# 2019_Dashboard_rev_1-15-19.net
KiCad netlist of a schematic drawn in EAGLE
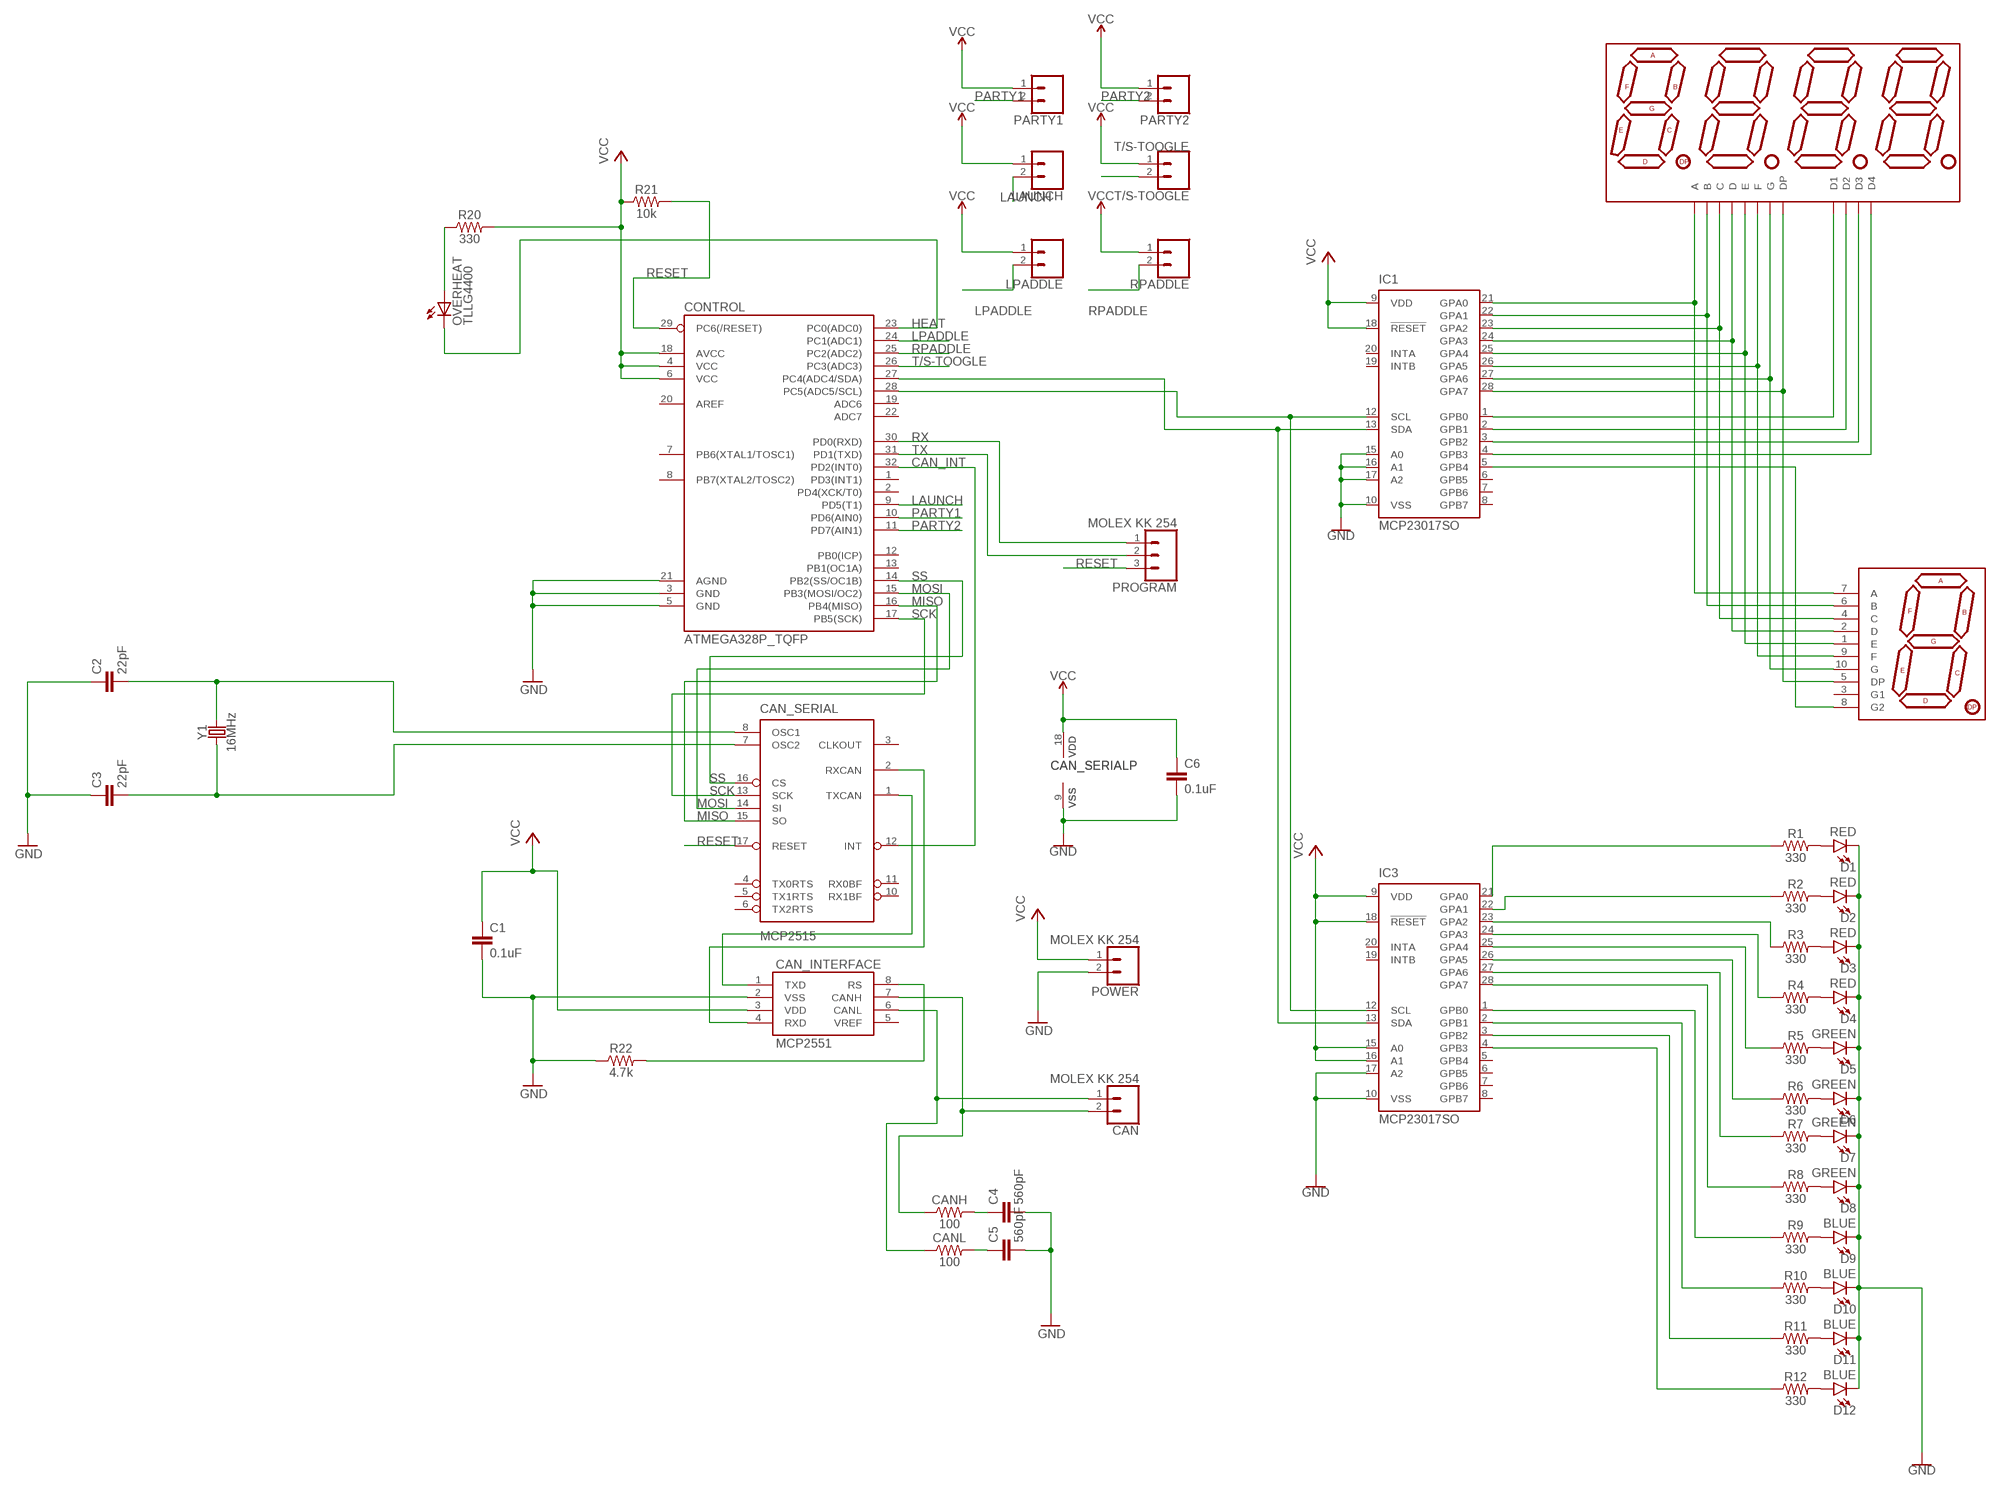
[diagram p0: schematic, sheet 1]

(export (version "E")
  (design (tool "Eeschema 10.0.6"))
  (components
    (comp (ref "C1")
      (value "0.1uF")
      (footprint "eagle-import:0603")
      (libsource (lib "eagle-import") (part "0.1UF-0603-25V-(+80/-20%)"))
    )
    (comp (ref "C2")
      (value "22pF")
      (footprint "eagle-import:0603")
      (libsource (lib "eagle-import") (part "22PF-0603-50V-5%"))
    )
    (comp (ref "C3")
      (value "22pF")
      (footprint "eagle-import:0603")
      (libsource (lib "eagle-import") (part "22PF-0603-50V-5%"))
    )
    (comp (ref "C4")
      (value "560pF")
      (footprint "eagle-import:0603")
      (libsource (lib "eagle-import") (part "560PF-0603-50V-5%"))
    )
    (comp (ref "C5")
      (value "560pF")
      (footprint "eagle-import:0603")
      (libsource (lib "eagle-import") (part "560PF-0603-50V-5%"))
    )
    (comp (ref "C6")
      (value "0.1uF")
      (footprint "eagle-import:0402")
      (libsource (lib "eagle-import") (part "0.1UF-0402-16V-10%"))
    )
    (comp (ref "CAN")
      (value "MOLEX KK 254")
      (footprint "eagle-import:1X02")
      (libsource (lib "eagle-import") (part "CONN_02"))
    )
    (comp (ref "CANH")
      (value "100")
      (footprint "eagle-import:0603")
      (libsource (lib "eagle-import") (part "100OHM-0603-1/4W-5%"))
    )
    (comp (ref "CANL")
      (value "100")
      (footprint "eagle-import:0603")
      (libsource (lib "eagle-import") (part "100OHM-0603-1/4W-5%"))
    )
    (comp (ref "CAN_INTERFACE")
      (value "MCP2551")
      (footprint "eagle-import:SO08")
      (libsource (lib "eagle-import") (part "MCP2551"))
    )
    (comp (ref "CAN_SERIAL")
      (value "MCP2515")
      (footprint "eagle-import:SO18W")
      (libsource (lib "eagle-import") (part "MCP2515(MCP2510)SO"))
    )
    (comp (ref "CONTROL")
      (value "ATMEGA328P_TQFP")
      (footprint "eagle-import:TQFP32-08")
      (libsource (lib "eagle-import") (part "ATMEGA328P_TQFP"))
    )
    (comp (ref "D1")
      (value "RED")
      (footprint "eagle-import:LED-1206")
      (libsource (lib "eagle-import") (part "LED-RED1206"))
    )
    (comp (ref "D2")
      (value "RED")
      (footprint "eagle-import:LED-1206")
      (libsource (lib "eagle-import") (part "LED-RED1206"))
    )
    (comp (ref "D3")
      (value "RED")
      (footprint "eagle-import:LED-1206")
      (libsource (lib "eagle-import") (part "LED-RED1206"))
    )
    (comp (ref "D4")
      (value "RED")
      (footprint "eagle-import:LED-1206")
      (libsource (lib "eagle-import") (part "LED-RED1206"))
    )
    (comp (ref "D5")
      (value "GREEN")
      (footprint "eagle-import:LED-1206")
      (libsource (lib "eagle-import") (part "LED-GREENLILYPAD"))
    )
    (comp (ref "D6")
      (value "GREEN")
      (footprint "eagle-import:LED-1206")
      (libsource (lib "eagle-import") (part "LED-GREENLILYPAD"))
    )
    (comp (ref "D7")
      (value "GREEN")
      (footprint "eagle-import:LED-1206")
      (libsource (lib "eagle-import") (part "LED-GREENLILYPAD"))
    )
    (comp (ref "D8")
      (value "GREEN")
      (footprint "eagle-import:LED-1206")
      (libsource (lib "eagle-import") (part "LED-GREENLILYPAD"))
    )
    (comp (ref "D9")
      (value "BLUE")
      (footprint "eagle-import:LED-1206")
      (libsource (lib "eagle-import") (part "LED-BLUE1206"))
    )
    (comp (ref "D10")
      (value "BLUE")
      (footprint "eagle-import:LED-1206")
      (libsource (lib "eagle-import") (part "LED-BLUE1206"))
    )
    (comp (ref "D11")
      (value "BLUE")
      (footprint "eagle-import:LED-1206")
      (libsource (lib "eagle-import") (part "LED-BLUE1206"))
    )
    (comp (ref "D12")
      (value "BLUE")
      (footprint "eagle-import:LED-1206")
      (libsource (lib "eagle-import") (part "LED-BLUE1206"))
    )
    (comp (ref "DISP1")
      (value "ATA8041ARBJ")
      (footprint "eagle-import:7-SEGMENT-4DIGIT-20MM")
      (libsource (lib "eagle-import") (part "7-SEGMENT-4DIGIT-20MM-RED"))
    )
    (comp (ref "IC1")
      (value "MCP23017SO")
      (footprint "eagle-import:SO28W")
      (libsource (lib "eagle-import") (part "MCP23017SO"))
    )
    (comp (ref "IC3")
      (value "MCP23017SO")
      (footprint "eagle-import:SO28W")
      (libsource (lib "eagle-import") (part "MCP23017SO"))
    )
    (comp (ref "LAUNCH")
      (value "CONN_02LOCK")
      (footprint "eagle-import:1X02_LOCK")
      (libsource (lib "eagle-import") (part "CONN_02LOCK"))
    )
    (comp (ref "LPADDLE")
      (value "CONN_02LOCK")
      (footprint "eagle-import:1X02_LOCK")
      (libsource (lib "eagle-import") (part "CONN_02LOCK"))
    )
    (comp (ref "OVERHEAT")
      (value "TLLG4400")
      (footprint "eagle-import:LED3MM")
      (fields (field (name "MF") "VISHAY SEMICONDUCTOR"))
      (libsource (lib "eagle-import") (part "TLLG4400"))
    )
    (comp (ref "PARTY1")
      (value "CONN_02LOCK")
      (footprint "eagle-import:1X02_LOCK")
      (libsource (lib "eagle-import") (part "CONN_02LOCK"))
    )
    (comp (ref "PARTY2")
      (value "CONN_02LOCK")
      (footprint "eagle-import:1X02_LOCK")
      (libsource (lib "eagle-import") (part "CONN_02LOCK"))
    )
    (comp (ref "POWER")
      (value "MOLEX KK 254")
      (footprint "eagle-import:1X02")
      (libsource (lib "eagle-import") (part "CONN_02"))
    )
    (comp (ref "PROGRAM")
      (value "MOLEX KK 254")
      (footprint "eagle-import:1X03")
      (libsource (lib "eagle-import") (part "CONN_03"))
    )
    (comp (ref "R1")
      (value "330")
      (footprint "eagle-import:0603")
      (libsource (lib "eagle-import") (part "330OHM-0603-1/10W-1%"))
    )
    (comp (ref "R2")
      (value "330")
      (footprint "eagle-import:0603")
      (libsource (lib "eagle-import") (part "330OHM-0603-1/10W-1%"))
    )
    (comp (ref "R3")
      (value "330")
      (footprint "eagle-import:0603")
      (libsource (lib "eagle-import") (part "330OHM-0603-1/10W-1%"))
    )
    (comp (ref "R4")
      (value "330")
      (footprint "eagle-import:0603")
      (libsource (lib "eagle-import") (part "330OHM-0603-1/10W-1%"))
    )
    (comp (ref "R5")
      (value "330")
      (footprint "eagle-import:0603")
      (libsource (lib "eagle-import") (part "330OHM-0603-1/10W-1%"))
    )
    (comp (ref "R6")
      (value "330")
      (footprint "eagle-import:0603")
      (libsource (lib "eagle-import") (part "330OHM-0603-1/10W-1%"))
    )
    (comp (ref "R7")
      (value "330")
      (footprint "eagle-import:0603")
      (libsource (lib "eagle-import") (part "330OHM-0603-1/10W-1%"))
    )
    (comp (ref "R8")
      (value "330")
      (footprint "eagle-import:0603")
      (libsource (lib "eagle-import") (part "330OHM-0603-1/10W-1%"))
    )
    (comp (ref "R9")
      (value "330")
      (footprint "eagle-import:0603")
      (libsource (lib "eagle-import") (part "330OHM-0603-1/10W-1%"))
    )
    (comp (ref "R10")
      (value "330")
      (footprint "eagle-import:0603")
      (libsource (lib "eagle-import") (part "330OHM-0603-1/10W-1%"))
    )
    (comp (ref "R11")
      (value "330")
      (footprint "eagle-import:0603")
      (libsource (lib "eagle-import") (part "330OHM-0603-1/10W-1%"))
    )
    (comp (ref "R12")
      (value "330")
      (footprint "eagle-import:0603")
      (libsource (lib "eagle-import") (part "330OHM-0603-1/10W-1%"))
    )
    (comp (ref "R20")
      (value "330")
      (footprint "eagle-import:0603")
      (libsource (lib "eagle-import") (part "330OHM-0603-1/10W-1%"))
    )
    (comp (ref "R21")
      (value "10k")
      (footprint "eagle-import:0603")
      (libsource (lib "eagle-import") (part "10KOHM-0603-1/10W-1%"))
    )
    (comp (ref "R22")
      (value "4.7k")
      (footprint "eagle-import:0603")
      (libsource (lib "eagle-import") (part "4.7KOHM-0603-1/10W-1%"))
    )
    (comp (ref "RPADDLE")
      (value "CONN_02LOCK")
      (footprint "eagle-import:1X02_LOCK")
      (libsource (lib "eagle-import") (part "CONN_02LOCK"))
    )
    (comp (ref "T/S-TOOGLE")
      (value "CONN_02LOCK")
      (footprint "eagle-import:1X02_LOCK")
      (libsource (lib "eagle-import") (part "CONN_02LOCK"))
    )
    (comp (ref "U$1")
      (value "YSD-1601AR4B-8")
      (footprint "eagle-import:7-SEGMENT-1_PTH")
      (libsource (lib "eagle-import") (part "7-SEGMENT-1DIGIT-1INCH-RED"))
    )
    (comp (ref "Y1")
      (value "16MHz")
      (footprint "eagle-import:HC49US")
      (libsource (lib "eagle-import") (part "CRYSTAL-16MHZPTH-HC49US"))
    )
  )
  (nets
    (net (code "1") (name "/CAN_INT") (class "Default")
      (node (ref "CAN_SERIAL") (pin "12") (pinfunction "INT_12") (pintype "output"))
      (node (ref "CONTROL") (pin "32") (pinfunction "PD2(INT0)_32") (pintype "bidirectional"))
    )
    (net (code "2") (name "/HEAT") (class "Default")
      (node (ref "CONTROL") (pin "23") (pinfunction "PC0(ADC0)_23") (pintype "bidirectional"))
      (node (ref "OVERHEAT") (pin "K") (pinfunction "C_K") (pintype "passive"))
    )
    (net (code "3") (name "/LAUNCH") (class "Default")
      (node (ref "CONTROL") (pin "9") (pinfunction "PD5(T1)_9") (pintype "bidirectional"))
      (node (ref "LAUNCH") (pin "2") (pinfunction "2_2") (pintype "passive"))
    )
    (net (code "4") (name "/LPADDLE") (class "Default")
      (node (ref "CONTROL") (pin "24") (pinfunction "PC1(ADC1)_24") (pintype "bidirectional"))
      (node (ref "LPADDLE") (pin "2") (pinfunction "2_2") (pintype "passive"))
    )
    (net (code "5") (name "/MISO") (class "Default")
      (node (ref "CAN_SERIAL") (pin "15") (pinfunction "SO_15") (pintype "output"))
      (node (ref "CONTROL") (pin "16") (pinfunction "PB4(MISO)_16") (pintype "bidirectional"))
    )
    (net (code "6") (name "/MOSI") (class "Default")
      (node (ref "CAN_SERIAL") (pin "14") (pinfunction "SI_14") (pintype "input"))
      (node (ref "CONTROL") (pin "15") (pinfunction "PB3(MOSI/OC2)_15") (pintype "bidirectional"))
    )
    (net (code "7") (name "/PARTY1") (class "Default")
      (node (ref "CONTROL") (pin "10") (pinfunction "PD6(AIN0)_10") (pintype "bidirectional"))
      (node (ref "PARTY1") (pin "2") (pinfunction "2_2") (pintype "passive"))
    )
    (net (code "8") (name "/PARTY2") (class "Default")
      (node (ref "CONTROL") (pin "11") (pinfunction "PD7(AIN1)_11") (pintype "bidirectional"))
      (node (ref "PARTY2") (pin "2") (pinfunction "2_2") (pintype "passive"))
    )
    (net (code "9") (name "/RESET") (class "Default")
      (node (ref "CAN_SERIAL") (pin "17") (pinfunction "RESET_17") (pintype "input"))
      (node (ref "CONTROL") (pin "29") (pinfunction "PC6(/RESET)_29") (pintype "bidirectional"))
      (node (ref "PROGRAM") (pin "3") (pinfunction "3_3") (pintype "passive"))
      (node (ref "R21") (pin "2") (pinfunction "2_2") (pintype "passive"))
    )
    (net (code "10") (name "/RPADDLE") (class "Default")
      (node (ref "CONTROL") (pin "25") (pinfunction "PC2(ADC2)_25") (pintype "bidirectional"))
      (node (ref "RPADDLE") (pin "2") (pinfunction "2_2") (pintype "passive"))
    )
    (net (code "11") (name "/RX") (class "Default")
      (node (ref "CONTROL") (pin "30") (pinfunction "PD0(RXD)_30") (pintype "bidirectional"))
      (node (ref "PROGRAM") (pin "1") (pinfunction "1_1") (pintype "passive"))
    )
    (net (code "12") (name "/SCK") (class "Default")
      (node (ref "CAN_SERIAL") (pin "13") (pinfunction "SCK_13") (pintype "input"))
      (node (ref "CONTROL") (pin "17") (pinfunction "PB5(SCK)_17") (pintype "bidirectional"))
    )
    (net (code "13") (name "/SS") (class "Default")
      (node (ref "CAN_SERIAL") (pin "16") (pinfunction "CS_16") (pintype "input"))
      (node (ref "CONTROL") (pin "14") (pinfunction "PB2(SS/OC1B)_14") (pintype "bidirectional"))
    )
    (net (code "14") (name "/TX") (class "Default")
      (node (ref "CONTROL") (pin "31") (pinfunction "PD1(TXD)_31") (pintype "bidirectional"))
      (node (ref "PROGRAM") (pin "2") (pinfunction "2_2") (pintype "passive"))
    )
    (net (code "15") (name "/T{slash}S-TOOGLE") (class "Default")
      (node (ref "CONTROL") (pin "26") (pinfunction "PC3(ADC3)_26") (pintype "bidirectional"))
      (node (ref "T/S-TOOGLE") (pin "2") (pinfunction "2_2") (pintype "passive"))
    )
    (net (code "16") (name "GND") (class "Default")
      (node (ref "C1") (pin "2") (pinfunction "2_2") (pintype "passive"))
      (node (ref "C2") (pin "1") (pinfunction "1_1") (pintype "passive"))
      (node (ref "C3") (pin "1") (pinfunction "1_1") (pintype "passive"))
      (node (ref "C4") (pin "2") (pinfunction "2_2") (pintype "passive"))
      (node (ref "C5") (pin "2") (pinfunction "2_2") (pintype "passive"))
      (node (ref "C6") (pin "2") (pinfunction "2_2") (pintype "passive"))
      (node (ref "CAN_INTERFACE") (pin "2") (pinfunction "VSS_2") (pintype "bidirectional"))
      (node (ref "CAN_SERIAL") (pin "9") (pinfunction "VSS_9") (pintype "power_in"))
      (node (ref "CONTROL") (pin "21") (pinfunction "AGND_21") (pintype "bidirectional"))
      (node (ref "CONTROL") (pin "3") (pinfunction "GND_3") (pintype "bidirectional"))
      (node (ref "CONTROL") (pin "5") (pinfunction "GND_5") (pintype "bidirectional"))
      (node (ref "D1") (pin "C") (pinfunction "C_C") (pintype "passive"))
      (node (ref "D10") (pin "C") (pinfunction "C_C") (pintype "passive"))
      (node (ref "D11") (pin "C") (pinfunction "C_C") (pintype "passive"))
      (node (ref "D12") (pin "C") (pinfunction "C_C") (pintype "passive"))
      (node (ref "D2") (pin "C") (pinfunction "C_C") (pintype "passive"))
      (node (ref "D3") (pin "C") (pinfunction "C_C") (pintype "passive"))
      (node (ref "D4") (pin "C") (pinfunction "C_C") (pintype "passive"))
      (node (ref "D5") (pin "C") (pinfunction "C_C") (pintype "passive"))
      (node (ref "D6") (pin "C") (pinfunction "C_C") (pintype "passive"))
      (node (ref "D7") (pin "C") (pinfunction "C_C") (pintype "passive"))
      (node (ref "D8") (pin "C") (pinfunction "C_C") (pintype "passive"))
      (node (ref "D9") (pin "C") (pinfunction "C_C") (pintype "passive"))
      (node (ref "IC1") (pin "10") (pinfunction "VSS_10") (pintype "power_in"))
      (node (ref "IC1") (pin "15") (pinfunction "A0_15") (pintype "input"))
      (node (ref "IC1") (pin "16") (pinfunction "A1_16") (pintype "input"))
      (node (ref "IC1") (pin "17") (pinfunction "A2_17") (pintype "input"))
      (node (ref "IC3") (pin "10") (pinfunction "VSS_10") (pintype "power_in"))
      (node (ref "IC3") (pin "17") (pinfunction "A2_17") (pintype "input"))
      (node (ref "POWER") (pin "2") (pinfunction "2_2") (pintype "passive"))
      (node (ref "R22") (pin "1") (pinfunction "1_1") (pintype "passive"))
    )
    (net (code "17") (name "Net-(C4-Pad1)") (class "Default")
      (node (ref "C4") (pin "1") (pinfunction "1_1") (pintype "passive"))
      (node (ref "CANH") (pin "2") (pinfunction "2_2") (pintype "passive"))
    )
    (net (code "18") (name "Net-(C5-Pad1)") (class "Default")
      (node (ref "C5") (pin "1") (pinfunction "1_1") (pintype "passive"))
      (node (ref "CANL") (pin "2") (pinfunction "2_2") (pintype "passive"))
    )
    (net (code "19") (name "Net-(CAN_INTERFACE-CANH)") (class "Default")
      (node (ref "CAN") (pin "2") (pinfunction "2_2") (pintype "passive"))
      (node (ref "CANH") (pin "1") (pinfunction "1_1") (pintype "passive"))
      (node (ref "CAN_INTERFACE") (pin "7") (pinfunction "CANH_7") (pintype "bidirectional"))
    )
    (net (code "20") (name "Net-(CAN_INTERFACE-CANL)") (class "Default")
      (node (ref "CAN") (pin "1") (pinfunction "1_1") (pintype "passive"))
      (node (ref "CANL") (pin "1") (pinfunction "1_1") (pintype "passive"))
      (node (ref "CAN_INTERFACE") (pin "6") (pinfunction "CANL_6") (pintype "bidirectional"))
    )
    (net (code "21") (name "Net-(CAN_INTERFACE-RS)") (class "Default")
      (node (ref "CAN_INTERFACE") (pin "8") (pinfunction "RS_8") (pintype "bidirectional"))
      (node (ref "R22") (pin "2") (pinfunction "2_2") (pintype "passive"))
    )
    (net (code "22") (name "Net-(CAN_INTERFACE-RXD)") (class "Default")
      (node (ref "CAN_INTERFACE") (pin "4") (pinfunction "RXD_4") (pintype "bidirectional"))
      (node (ref "CAN_SERIAL") (pin "2") (pinfunction "RXCAN_2") (pintype "input"))
    )
    (net (code "23") (name "Net-(CAN_INTERFACE-TXD)") (class "Default")
      (node (ref "CAN_INTERFACE") (pin "1") (pinfunction "TXD_1") (pintype "bidirectional"))
      (node (ref "CAN_SERIAL") (pin "1") (pinfunction "TXCAN_1") (pintype "output"))
    )
    (net (code "24") (name "Net-(CAN_SERIALA-OSC1)") (class "Default")
      (node (ref "C2") (pin "2") (pinfunction "2_2") (pintype "passive"))
      (node (ref "CAN_SERIAL") (pin "8") (pinfunction "OSC1_8") (pintype "input"))
      (node (ref "Y1") (pin "2") (pinfunction "2_2") (pintype "passive"))
    )
    (net (code "25") (name "Net-(CAN_SERIALA-OSC2)") (class "Default")
      (node (ref "C3") (pin "2") (pinfunction "2_2") (pintype "passive"))
      (node (ref "CAN_SERIAL") (pin "7") (pinfunction "OSC2_7") (pintype "output"))
      (node (ref "Y1") (pin "1") (pinfunction "1_1") (pintype "passive"))
    )
    (net (code "26") (name "Net-(CONTROL-PC4(ADC4{slash}SDA))") (class "Default")
      (node (ref "CONTROL") (pin "27") (pinfunction "PC4(ADC4/SDA)_27") (pintype "bidirectional"))
      (node (ref "IC1") (pin "13") (pinfunction "SDA_13") (pintype "bidirectional"))
      (node (ref "IC3") (pin "13") (pinfunction "SDA_13") (pintype "bidirectional"))
    )
    (net (code "27") (name "Net-(CONTROL-PC5(ADC5{slash}SCL))") (class "Default")
      (node (ref "CONTROL") (pin "28") (pinfunction "PC5(ADC5/SCL)_28") (pintype "bidirectional"))
      (node (ref "IC1") (pin "12") (pinfunction "SCL_12") (pintype "input"))
      (node (ref "IC3") (pin "12") (pinfunction "SCL_12") (pintype "input"))
    )
    (net (code "28") (name "Net-(D1-PadA)") (class "Default")
      (node (ref "D1") (pin "A") (pinfunction "A_A") (pintype "passive"))
      (node (ref "R1") (pin "2") (pinfunction "2_2") (pintype "passive"))
    )
    (net (code "29") (name "Net-(D2-PadA)") (class "Default")
      (node (ref "D2") (pin "A") (pinfunction "A_A") (pintype "passive"))
      (node (ref "R2") (pin "2") (pinfunction "2_2") (pintype "passive"))
    )
    (net (code "30") (name "Net-(D3-PadA)") (class "Default")
      (node (ref "D3") (pin "A") (pinfunction "A_A") (pintype "passive"))
      (node (ref "R3") (pin "2") (pinfunction "2_2") (pintype "passive"))
    )
    (net (code "31") (name "Net-(D4-PadA)") (class "Default")
      (node (ref "D4") (pin "A") (pinfunction "A_A") (pintype "passive"))
      (node (ref "R4") (pin "2") (pinfunction "2_2") (pintype "passive"))
    )
    (net (code "32") (name "Net-(D5-PadA)") (class "Default")
      (node (ref "D5") (pin "A") (pinfunction "A_A") (pintype "passive"))
      (node (ref "R5") (pin "2") (pinfunction "2_2") (pintype "passive"))
    )
    (net (code "33") (name "Net-(D6-PadA)") (class "Default")
      (node (ref "D6") (pin "A") (pinfunction "A_A") (pintype "passive"))
      (node (ref "R6") (pin "2") (pinfunction "2_2") (pintype "passive"))
    )
    (net (code "34") (name "Net-(D7-PadA)") (class "Default")
      (node (ref "D7") (pin "A") (pinfunction "A_A") (pintype "passive"))
      (node (ref "R7") (pin "2") (pinfunction "2_2") (pintype "passive"))
    )
    (net (code "35") (name "Net-(D8-PadA)") (class "Default")
      (node (ref "D8") (pin "A") (pinfunction "A_A") (pintype "passive"))
      (node (ref "R8") (pin "2") (pinfunction "2_2") (pintype "passive"))
    )
    (net (code "36") (name "Net-(D9-PadA)") (class "Default")
      (node (ref "D9") (pin "A") (pinfunction "A_A") (pintype "passive"))
      (node (ref "R9") (pin "2") (pinfunction "2_2") (pintype "passive"))
    )
    (net (code "37") (name "Net-(D10-PadA)") (class "Default")
      (node (ref "D10") (pin "A") (pinfunction "A_A") (pintype "passive"))
      (node (ref "R10") (pin "2") (pinfunction "2_2") (pintype "passive"))
    )
    (net (code "38") (name "Net-(D11-PadA)") (class "Default")
      (node (ref "D11") (pin "A") (pinfunction "A_A") (pintype "passive"))
      (node (ref "R11") (pin "2") (pinfunction "2_2") (pintype "passive"))
    )
    (net (code "39") (name "Net-(D12-PadA)") (class "Default")
      (node (ref "D12") (pin "A") (pinfunction "A_A") (pintype "passive"))
      (node (ref "R12") (pin "2") (pinfunction "2_2") (pintype "passive"))
    )
    (net (code "40") (name "Net-(DISP1-A)") (class "Default")
      (node (ref "DISP1") (pin "11") (pinfunction "A_11") (pintype "bidirectional"))
      (node (ref "IC1") (pin "21") (pinfunction "GPA0_21") (pintype "bidirectional"))
      (node (ref "U$1") (pin "7") (pinfunction "A_7") (pintype "bidirectional"))
    )
    (net (code "41") (name "Net-(DISP1-B)") (class "Default")
      (node (ref "DISP1") (pin "7") (pinfunction "B_7") (pintype "bidirectional"))
      (node (ref "IC1") (pin "22") (pinfunction "GPA1_22") (pintype "bidirectional"))
      (node (ref "U$1") (pin "6") (pinfunction "B_6") (pintype "bidirectional"))
    )
    (net (code "42") (name "Net-(DISP1-C)") (class "Default")
      (node (ref "DISP1") (pin "4") (pinfunction "C_4") (pintype "bidirectional"))
      (node (ref "IC1") (pin "23") (pinfunction "GPA2_23") (pintype "bidirectional"))
      (node (ref "U$1") (pin "4") (pinfunction "C_4") (pintype "bidirectional"))
    )
    (net (code "43") (name "Net-(DISP1-D)") (class "Default")
      (node (ref "DISP1") (pin "2") (pinfunction "D_2") (pintype "bidirectional"))
      (node (ref "IC1") (pin "24") (pinfunction "GPA3_24") (pintype "bidirectional"))
      (node (ref "U$1") (pin "2") (pinfunction "D_2") (pintype "bidirectional"))
    )
    (net (code "44") (name "Net-(DISP1-D1)") (class "Default")
      (node (ref "DISP1") (pin "12") (pinfunction "D1_12") (pintype "bidirectional"))
      (node (ref "IC1") (pin "1") (pinfunction "GPB0_1") (pintype "bidirectional"))
    )
    (net (code "45") (name "Net-(DISP1-D2)") (class "Default")
      (node (ref "DISP1") (pin "9") (pinfunction "D2_9") (pintype "bidirectional"))
      (node (ref "IC1") (pin "2") (pinfunction "GPB1_2") (pintype "bidirectional"))
    )
    (net (code "46") (name "Net-(DISP1-D3)") (class "Default")
      (node (ref "DISP1") (pin "8") (pinfunction "D3_8") (pintype "bidirectional"))
      (node (ref "IC1") (pin "3") (pinfunction "GPB2_3") (pintype "bidirectional"))
    )
    (net (code "47") (name "Net-(DISP1-D4)") (class "Default")
      (node (ref "DISP1") (pin "6") (pinfunction "D4_6") (pintype "bidirectional"))
      (node (ref "IC1") (pin "4") (pinfunction "GPB3_4") (pintype "bidirectional"))
    )
    (net (code "48") (name "Net-(DISP1-DP)") (class "Default")
      (node (ref "DISP1") (pin "3") (pinfunction "DP_3") (pintype "bidirectional"))
      (node (ref "IC1") (pin "28") (pinfunction "GPA7_28") (pintype "bidirectional"))
      (node (ref "U$1") (pin "5") (pinfunction "DP_5") (pintype "bidirectional"))
    )
    (net (code "49") (name "Net-(DISP1-E)") (class "Default")
      (node (ref "DISP1") (pin "1") (pinfunction "E_1") (pintype "bidirectional"))
      (node (ref "IC1") (pin "25") (pinfunction "GPA4_25") (pintype "bidirectional"))
      (node (ref "U$1") (pin "1") (pinfunction "E_1") (pintype "bidirectional"))
    )
    (net (code "50") (name "Net-(DISP1-F)") (class "Default")
      (node (ref "DISP1") (pin "10") (pinfunction "F_10") (pintype "bidirectional"))
      (node (ref "IC1") (pin "26") (pinfunction "GPA5_26") (pintype "bidirectional"))
      (node (ref "U$1") (pin "9") (pinfunction "F_9") (pintype "bidirectional"))
    )
    (net (code "51") (name "Net-(DISP1-G)") (class "Default")
      (node (ref "DISP1") (pin "5") (pinfunction "G_5") (pintype "bidirectional"))
      (node (ref "IC1") (pin "27") (pinfunction "GPA6_27") (pintype "bidirectional"))
      (node (ref "U$1") (pin "10") (pinfunction "G_10") (pintype "bidirectional"))
    )
    (net (code "52") (name "Net-(IC1-GPB4)") (class "Default")
      (node (ref "IC1") (pin "5") (pinfunction "GPB4_5") (pintype "bidirectional"))
      (node (ref "U$1") (pin "8") (pinfunction "G2_8") (pintype "bidirectional"))
    )
    (net (code "53") (name "Net-(IC3-GPA0)") (class "Default")
      (node (ref "IC3") (pin "21") (pinfunction "GPA0_21") (pintype "bidirectional"))
      (node (ref "R1") (pin "1") (pinfunction "1_1") (pintype "passive"))
    )
    (net (code "54") (name "Net-(IC3-GPA1)") (class "Default")
      (node (ref "IC3") (pin "22") (pinfunction "GPA1_22") (pintype "bidirectional"))
      (node (ref "R2") (pin "1") (pinfunction "1_1") (pintype "passive"))
    )
    (net (code "55") (name "Net-(IC3-GPA2)") (class "Default")
      (node (ref "IC3") (pin "23") (pinfunction "GPA2_23") (pintype "bidirectional"))
      (node (ref "R3") (pin "1") (pinfunction "1_1") (pintype "passive"))
    )
    (net (code "56") (name "Net-(IC3-GPA3)") (class "Default")
      (node (ref "IC3") (pin "24") (pinfunction "GPA3_24") (pintype "bidirectional"))
      (node (ref "R4") (pin "1") (pinfunction "1_1") (pintype "passive"))
    )
    (net (code "57") (name "Net-(IC3-GPA4)") (class "Default")
      (node (ref "IC3") (pin "25") (pinfunction "GPA4_25") (pintype "bidirectional"))
      (node (ref "R5") (pin "1") (pinfunction "1_1") (pintype "passive"))
    )
    (net (code "58") (name "Net-(IC3-GPA5)") (class "Default")
      (node (ref "IC3") (pin "26") (pinfunction "GPA5_26") (pintype "bidirectional"))
      (node (ref "R6") (pin "1") (pinfunction "1_1") (pintype "passive"))
    )
    (net (code "59") (name "Net-(IC3-GPA6)") (class "Default")
      (node (ref "IC3") (pin "27") (pinfunction "GPA6_27") (pintype "bidirectional"))
      (node (ref "R7") (pin "1") (pinfunction "1_1") (pintype "passive"))
    )
    (net (code "60") (name "Net-(IC3-GPA7)") (class "Default")
      (node (ref "IC3") (pin "28") (pinfunction "GPA7_28") (pintype "bidirectional"))
      (node (ref "R8") (pin "1") (pinfunction "1_1") (pintype "passive"))
    )
    (net (code "61") (name "Net-(IC3-GPB0)") (class "Default")
      (node (ref "IC3") (pin "1") (pinfunction "GPB0_1") (pintype "bidirectional"))
      (node (ref "R9") (pin "1") (pinfunction "1_1") (pintype "passive"))
    )
    (net (code "62") (name "Net-(IC3-GPB1)") (class "Default")
      (node (ref "IC3") (pin "2") (pinfunction "GPB1_2") (pintype "bidirectional"))
      (node (ref "R10") (pin "1") (pinfunction "1_1") (pintype "passive"))
    )
    (net (code "63") (name "Net-(IC3-GPB2)") (class "Default")
      (node (ref "IC3") (pin "3") (pinfunction "GPB2_3") (pintype "bidirectional"))
      (node (ref "R11") (pin "1") (pinfunction "1_1") (pintype "passive"))
    )
    (net (code "64") (name "Net-(IC3-GPB3)") (class "Default")
      (node (ref "IC3") (pin "4") (pinfunction "GPB3_4") (pintype "bidirectional"))
      (node (ref "R12") (pin "1") (pinfunction "1_1") (pintype "passive"))
    )
    (net (code "65") (name "Net-(OVERHEAT-PadA)") (class "Default")
      (node (ref "OVERHEAT") (pin "A") (pinfunction "A_A") (pintype "passive"))
      (node (ref "R20") (pin "1") (pinfunction "1_1") (pintype "passive"))
    )
    (net (code "66") (name "VCC") (class "Default")
      (node (ref "C1") (pin "1") (pinfunction "1_1") (pintype "passive"))
      (node (ref "C6") (pin "1") (pinfunction "1_1") (pintype "passive"))
      (node (ref "CAN_INTERFACE") (pin "3") (pinfunction "VDD_3") (pintype "bidirectional"))
      (node (ref "CAN_SERIAL") (pin "18") (pinfunction "VDD_18") (pintype "power_in"))
      (node (ref "CONTROL") (pin "18") (pinfunction "AVCC_18") (pintype "bidirectional"))
      (node (ref "CONTROL") (pin "4") (pinfunction "VCC_4") (pintype "bidirectional"))
      (node (ref "CONTROL") (pin "6") (pinfunction "VCC_6") (pintype "bidirectional"))
      (node (ref "IC1") (pin "18") (pinfunction "~{RESET}_18") (pintype "input"))
      (node (ref "IC1") (pin "9") (pinfunction "VDD_9") (pintype "power_in"))
      (node (ref "IC3") (pin "15") (pinfunction "A0_15") (pintype "input"))
      (node (ref "IC3") (pin "16") (pinfunction "A1_16") (pintype "input"))
      (node (ref "IC3") (pin "18") (pinfunction "~{RESET}_18") (pintype "input"))
      (node (ref "IC3") (pin "9") (pinfunction "VDD_9") (pintype "power_in"))
      (node (ref "LAUNCH") (pin "1") (pinfunction "1_1") (pintype "passive"))
      (node (ref "LPADDLE") (pin "1") (pinfunction "1_1") (pintype "passive"))
      (node (ref "PARTY1") (pin "1") (pinfunction "1_1") (pintype "passive"))
      (node (ref "PARTY2") (pin "1") (pinfunction "1_1") (pintype "passive"))
      (node (ref "POWER") (pin "1") (pinfunction "1_1") (pintype "passive"))
      (node (ref "R20") (pin "2") (pinfunction "2_2") (pintype "passive"))
      (node (ref "R21") (pin "1") (pinfunction "1_1") (pintype "passive"))
      (node (ref "RPADDLE") (pin "1") (pinfunction "1_1") (pintype "passive"))
      (node (ref "T/S-TOOGLE") (pin "1") (pinfunction "1_1") (pintype "passive"))
    )
    (net (code "67") (name "unconnected-(CAN_INTERFACE-VREF-Pad5)") (class "Default")
      (node (ref "CAN_INTERFACE") (pin "5") (pinfunction "VREF_5") (pintype "bidirectional"))
    )
    (net (code "68") (name "unconnected-(CAN_SERIALA-CLKOUT-Pad3)") (class "Default")
      (node (ref "CAN_SERIAL") (pin "3") (pinfunction "CLKOUT_3") (pintype "output"))
    )
    (net (code "69") (name "unconnected-(CAN_SERIALA-RX0BF-Pad11)") (class "Default")
      (node (ref "CAN_SERIAL") (pin "11") (pinfunction "RX0BF_11") (pintype "output"))
    )
    (net (code "70") (name "unconnected-(CAN_SERIALA-RX1BF-Pad10)") (class "Default")
      (node (ref "CAN_SERIAL") (pin "10") (pinfunction "RX1BF_10") (pintype "output"))
    )
    (net (code "71") (name "unconnected-(CAN_SERIALA-TX0RTS-Pad4)") (class "Default")
      (node (ref "CAN_SERIAL") (pin "4") (pinfunction "TX0RTS_4") (pintype "input"))
    )
    (net (code "72") (name "unconnected-(CAN_SERIALA-TX1RTS-Pad5)") (class "Default")
      (node (ref "CAN_SERIAL") (pin "5") (pinfunction "TX1RTS_5") (pintype "input"))
    )
    (net (code "73") (name "unconnected-(CAN_SERIALA-TX2RTS-Pad6)") (class "Default")
      (node (ref "CAN_SERIAL") (pin "6") (pinfunction "TX2RTS_6") (pintype "input"))
    )
    (net (code "74") (name "unconnected-(CONTROL-ADC6-Pad19)") (class "Default")
      (node (ref "CONTROL") (pin "19") (pinfunction "ADC6_19") (pintype "bidirectional"))
    )
    (net (code "75") (name "unconnected-(CONTROL-ADC7-Pad22)") (class "Default")
      (node (ref "CONTROL") (pin "22") (pinfunction "ADC7_22") (pintype "bidirectional"))
    )
    (net (code "76") (name "unconnected-(CONTROL-AREF-Pad20)") (class "Default")
      (node (ref "CONTROL") (pin "20") (pinfunction "AREF_20") (pintype "bidirectional"))
    )
    (net (code "77") (name "unconnected-(CONTROL-PB0(ICP)-Pad12)") (class "Default")
      (node (ref "CONTROL") (pin "12") (pinfunction "PB0(ICP)_12") (pintype "bidirectional"))
    )
    (net (code "78") (name "unconnected-(CONTROL-PB1(OC1A)-Pad13)") (class "Default")
      (node (ref "CONTROL") (pin "13") (pinfunction "PB1(OC1A)_13") (pintype "bidirectional"))
    )
    (net (code "79") (name "unconnected-(CONTROL-PB6(XTAL1{slash}TOSC1)-Pad7)") (class "Default")
      (node (ref "CONTROL") (pin "7") (pinfunction "PB6(XTAL1/TOSC1)_7") (pintype "bidirectional"))
    )
    (net (code "80") (name "unconnected-(CONTROL-PB7(XTAL2{slash}TOSC2)-Pad8)") (class "Default")
      (node (ref "CONTROL") (pin "8") (pinfunction "PB7(XTAL2/TOSC2)_8") (pintype "bidirectional"))
    )
    (net (code "81") (name "unconnected-(CONTROL-PD3(INT1)-Pad1)") (class "Default")
      (node (ref "CONTROL") (pin "1") (pinfunction "PD3(INT1)_1") (pintype "bidirectional"))
    )
    (net (code "82") (name "unconnected-(CONTROL-PD4(XCK{slash}T0)-Pad2)") (class "Default")
      (node (ref "CONTROL") (pin "2") (pinfunction "PD4(XCK/T0)_2") (pintype "bidirectional"))
    )
    (net (code "83") (name "unconnected-(IC1-GPB5-Pad6)") (class "Default")
      (node (ref "IC1") (pin "6") (pinfunction "GPB5_6") (pintype "bidirectional"))
    )
    (net (code "84") (name "unconnected-(IC1-GPB6-Pad7)") (class "Default")
      (node (ref "IC1") (pin "7") (pinfunction "GPB6_7") (pintype "bidirectional"))
    )
    (net (code "85") (name "unconnected-(IC1-GPB7-Pad8)") (class "Default")
      (node (ref "IC1") (pin "8") (pinfunction "GPB7_8") (pintype "bidirectional"))
    )
    (net (code "86") (name "unconnected-(IC1-INTA-Pad20)") (class "Default")
      (node (ref "IC1") (pin "20") (pinfunction "INTA_20") (pintype "output"))
    )
    (net (code "87") (name "unconnected-(IC1-INTB-Pad19)") (class "Default")
      (node (ref "IC1") (pin "19") (pinfunction "INTB_19") (pintype "output"))
    )
    (net (code "88") (name "unconnected-(IC3-GPB4-Pad5)") (class "Default")
      (node (ref "IC3") (pin "5") (pinfunction "GPB4_5") (pintype "bidirectional"))
    )
    (net (code "89") (name "unconnected-(IC3-GPB5-Pad6)") (class "Default")
      (node (ref "IC3") (pin "6") (pinfunction "GPB5_6") (pintype "bidirectional"))
    )
    (net (code "90") (name "unconnected-(IC3-GPB6-Pad7)") (class "Default")
      (node (ref "IC3") (pin "7") (pinfunction "GPB6_7") (pintype "bidirectional"))
    )
    (net (code "91") (name "unconnected-(IC3-GPB7-Pad8)") (class "Default")
      (node (ref "IC3") (pin "8") (pinfunction "GPB7_8") (pintype "bidirectional"))
    )
    (net (code "92") (name "unconnected-(IC3-INTA-Pad20)") (class "Default")
      (node (ref "IC3") (pin "20") (pinfunction "INTA_20") (pintype "output"))
    )
    (net (code "93") (name "unconnected-(IC3-INTB-Pad19)") (class "Default")
      (node (ref "IC3") (pin "19") (pinfunction "INTB_19") (pintype "output"))
    )
    (net (code "94") (name "unconnected-(U$1-G1-Pad3)") (class "Default")
      (node (ref "U$1") (pin "3") (pinfunction "G1_3") (pintype "bidirectional"))
    )
  )
)
